# Peripherals.net
KiCad netlist of a schematic drawn in Altium Designer
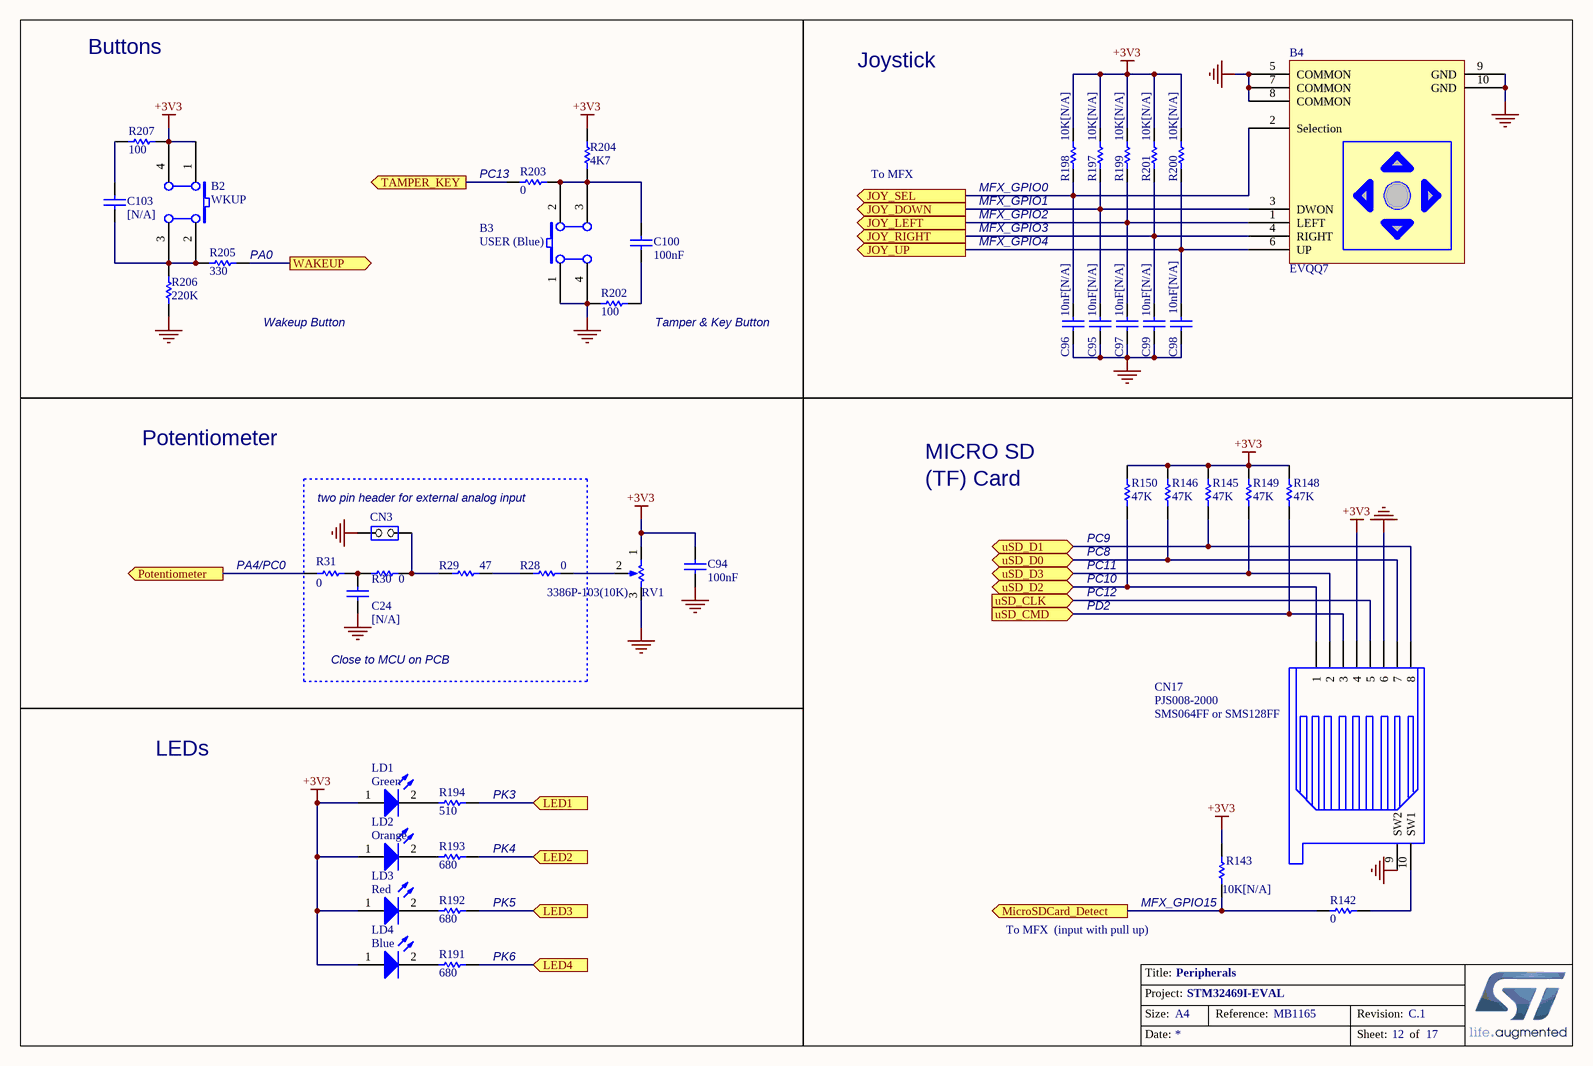
[diagram p0: Peripherals.SchDoc]

(export (version "E")
  (design (tool "Eeschema 10.0.6"))
  (components
    (comp (ref "B2")
      (value "WKUP")
      (footprint "PB10")
      (description "SE PUSHBUTTON")
      (libsource (lib "Documents") (part "SW PUSHBUTTON"))
    )
    (comp (ref "B3")
      (value "USER (Blue)")
      (footprint "PB10")
      (description "SE PUSHBUTTON")
      (libsource (lib "Documents") (part "SW PUSHBUTTON"))
    )
    (comp (ref "B4") (value "EVQQ7") (footprint "SW-JOY") (libsource (lib "mb1045") (part "EVQQ7")))
    (comp (ref "C24")
      (value "[N/A]")
      (footprint "0603C")
      (description "Capacitor")
      (fields (field (name "PUBLISHER") "Altium Limited"))
      (libsource (lib "Miscellaneous Devices") (part "cap"))
    )
    (comp (ref "C94")
      (value "100nF")
      (footprint "0603C")
      (description "Capacitor")
      (fields (field (name "PUBLISHER") "Altium Limited"))
      (libsource (lib "Miscellaneous Devices") (part "CAP"))
    )
    (comp (ref "C95")
      (value "10nF[N/A]")
      (footprint "0603C")
      (description "Capacitor")
      (fields (field (name "PUBLISHER") "Altium Limited"))
      (libsource (lib "Miscellaneous Devices") (part "CAP"))
    )
    (comp (ref "C96")
      (value "10nF[N/A]")
      (footprint "0603C")
      (description "Capacitor")
      (fields (field (name "PUBLISHER") "Altium Limited"))
      (libsource (lib "Miscellaneous Devices") (part "CAP"))
    )
    (comp (ref "C97")
      (value "10nF[N/A]")
      (footprint "0603C")
      (description "Capacitor")
      (fields (field (name "PUBLISHER") "Altium Limited"))
      (libsource (lib "Miscellaneous Devices") (part "CAP"))
    )
    (comp (ref "C98")
      (value "10nF[N/A]")
      (footprint "0603C")
      (description "Capacitor")
      (fields (field (name "PUBLISHER") "Altium Limited"))
      (libsource (lib "Miscellaneous Devices") (part "CAP"))
    )
    (comp (ref "C99")
      (value "10nF[N/A]")
      (footprint "0603C")
      (description "Capacitor")
      (fields (field (name "PUBLISHER") "Altium Limited"))
      (libsource (lib "Miscellaneous Devices") (part "CAP"))
    )
    (comp (ref "C100")
      (value "100nF")
      (footprint "0603C")
      (description "Capacitor")
      (fields (field (name "PUBLISHER") "Altium Limited"))
      (libsource (lib "Miscellaneous Devices") (part "CAP"))
    )
    (comp (ref "C103")
      (value "[N/A]")
      (footprint "0603C")
      (description "Capacitor")
      (fields (field (name "PUBLISHER") "Altium Limited"))
      (libsource (lib "Miscellaneous Devices") (part "CAP"))
    )
    (comp (ref "CN3") (value "~") (footprint "SIP2") (libsource (lib "*") (part "JP2")))
    (comp (ref "CN17")
      (value "PJS008-2000")
      (footprint "MSD_PJS008_")
      (libsource (lib "MB525") (part "SMS016AFA5E"))
    )
    (comp (ref "LD1")
      (value "Green")
      (footprint "0603D")
      (description "Typical RED, GREEN, YELLOW, AMBER GaAs LED")
      (fields (field (name "PUBLISHER") "Altium Limited"))
      (libsource (lib "Miscellaneous Devices") (part "LED2"))
    )
    (comp (ref "LD2")
      (value "Orange")
      (footprint "0603D")
      (description "Typical RED, GREEN, YELLOW, AMBER GaAs LED")
      (fields (field (name "PUBLISHER") "Altium Limited"))
      (libsource (lib "Miscellaneous Devices") (part "LED2"))
    )
    (comp (ref "LD3")
      (value "Red")
      (footprint "0603D")
      (description "Typical RED, GREEN, YELLOW, AMBER GaAs LED")
      (fields (field (name "PUBLISHER") "Altium Limited"))
      (libsource (lib "Miscellaneous Devices") (part "LED2"))
    )
    (comp (ref "LD4")
      (value "Blue")
      (footprint "0603D")
      (description "Typical RED, GREEN, YELLOW, AMBER GaAs LED")
      (fields (field (name "PUBLISHER") "Altium Limited"))
      (libsource (lib "Miscellaneous Devices") (part "LED2"))
    )
    (comp (ref "R28")
      (value "0")
      (footprint "0603R")
      (description "Resistor")
      (fields (field (name "PUBLISHER") "Altium Limited"))
      (libsource (lib "Miscellaneous Devices") (part "Res1"))
    )
    (comp (ref "R29")
      (value "47")
      (footprint "0603R")
      (description "Resistor")
      (fields (field (name "PUBLISHER") "Altium Limited"))
      (libsource (lib "Miscellaneous Devices") (part "Res1"))
    )
    (comp (ref "R30")
      (value "0")
      (footprint "0603R")
      (description "Resistor")
      (fields (field (name "PUBLISHER") "Altium Limited"))
      (libsource (lib "Miscellaneous Devices") (part "Res1"))
    )
    (comp (ref "R31")
      (value "0")
      (footprint "0603R")
      (description "Resistor")
      (fields (field (name "PUBLISHER") "Altium Limited"))
      (libsource (lib "Miscellaneous Devices") (part "Res1"))
    )
    (comp (ref "R142")
      (value "0")
      (footprint "0603R")
      (description "Resistor")
      (fields (field (name "PUBLISHER") "Altium Limited"))
      (libsource (lib "Miscellaneous Devices") (part "Res1"))
    )
    (comp (ref "R143")
      (value "10K[N/A]")
      (footprint "0603R")
      (description "Resistor")
      (fields (field (name "PUBLISHER") "Altium Limited"))
      (libsource (lib "Miscellaneous Devices") (part "Res1"))
    )
    (comp (ref "R145")
      (value "47K")
      (footprint "0603R")
      (description "Resistor")
      (fields (field (name "PUBLISHER") "Altium Limited"))
      (libsource (lib "Miscellaneous Devices") (part "res1"))
    )
    (comp (ref "R146")
      (value "47K")
      (footprint "0603R")
      (description "Resistor")
      (fields (field (name "PUBLISHER") "Altium Limited"))
      (libsource (lib "Miscellaneous Devices") (part "res1"))
    )
    (comp (ref "R148")
      (value "47K")
      (footprint "0603R")
      (description "Resistor")
      (fields (field (name "PUBLISHER") "Altium Limited"))
      (libsource (lib "Miscellaneous Devices") (part "res1"))
    )
    (comp (ref "R149")
      (value "47K")
      (footprint "0603R")
      (description "Resistor")
      (fields (field (name "PUBLISHER") "Altium Limited"))
      (libsource (lib "Miscellaneous Devices") (part "res1"))
    )
    (comp (ref "R150")
      (value "47K")
      (footprint "0603R")
      (description "Resistor")
      (fields (field (name "PUBLISHER") "Altium Limited"))
      (libsource (lib "Miscellaneous Devices") (part "res1"))
    )
    (comp (ref "R191")
      (value "680")
      (footprint "0603R")
      (description "Resistor")
      (fields (field (name "PUBLISHER") "Altium Limited"))
      (libsource (lib "Miscellaneous Devices") (part "Res1"))
    )
    (comp (ref "R192")
      (value "680")
      (footprint "0603R")
      (description "Resistor")
      (fields (field (name "PUBLISHER") "Altium Limited"))
      (libsource (lib "Miscellaneous Devices") (part "Res1"))
    )
    (comp (ref "R193")
      (value "680")
      (footprint "0603R")
      (description "Resistor")
      (fields (field (name "PUBLISHER") "Altium Limited"))
      (libsource (lib "Miscellaneous Devices") (part "Res1"))
    )
    (comp (ref "R194")
      (value "510")
      (footprint "0603R")
      (description "Resistor")
      (fields (field (name "PUBLISHER") "Altium Limited"))
      (libsource (lib "Miscellaneous Devices") (part "Res1"))
    )
    (comp (ref "R197")
      (value "10K[N/A]")
      (footprint "0603R")
      (description "Resistor")
      (fields (field (name "PUBLISHER") "Altium Limited"))
      (libsource (lib "Miscellaneous Devices") (part "res1"))
    )
    (comp (ref "R198")
      (value "10K[N/A]")
      (footprint "0603R")
      (description "Resistor")
      (fields (field (name "PUBLISHER") "Altium Limited"))
      (libsource (lib "Miscellaneous Devices") (part "res1"))
    )
    (comp (ref "R199")
      (value "10K[N/A]")
      (footprint "0603R")
      (description "Resistor")
      (fields (field (name "PUBLISHER") "Altium Limited"))
      (libsource (lib "Miscellaneous Devices") (part "res1"))
    )
    (comp (ref "R200")
      (value "10K[N/A]")
      (footprint "0603R")
      (description "Resistor")
      (fields (field (name "PUBLISHER") "Altium Limited"))
      (libsource (lib "Miscellaneous Devices") (part "res1"))
    )
    (comp (ref "R201")
      (value "10K[N/A]")
      (footprint "0603R")
      (description "Resistor")
      (fields (field (name "PUBLISHER") "Altium Limited"))
      (libsource (lib "Miscellaneous Devices") (part "res1"))
    )
    (comp (ref "R202")
      (value "100")
      (footprint "0603R")
      (description "Resistor")
      (fields (field (name "PUBLISHER") "Altium Limited"))
      (libsource (lib "Miscellaneous Devices") (part "Res1"))
    )
    (comp (ref "R203")
      (value "0")
      (footprint "0603R")
      (description "Resistor")
      (fields (field (name "PUBLISHER") "Altium Limited"))
      (libsource (lib "Miscellaneous Devices") (part "Res1"))
    )
    (comp (ref "R204")
      (value "4K7")
      (footprint "0603R")
      (description "Resistor")
      (fields (field (name "PUBLISHER") "Altium Limited"))
      (libsource (lib "Miscellaneous Devices") (part "res1"))
    )
    (comp (ref "R205")
      (value "330")
      (footprint "0603R")
      (description "Resistor")
      (fields (field (name "PUBLISHER") "Altium Limited"))
      (libsource (lib "Miscellaneous Devices") (part "Res1"))
    )
    (comp (ref "R206")
      (value "220K")
      (footprint "0603R")
      (description "Resistor")
      (fields (field (name "PUBLISHER") "Altium Limited"))
      (libsource (lib "Miscellaneous Devices") (part "res1"))
    )
    (comp (ref "R207")
      (value "100")
      (footprint "0603R")
      (description "Resistor")
      (fields (field (name "PUBLISHER") "Altium Limited"))
      (libsource (lib "Miscellaneous Devices") (part "Res1"))
    )
    (comp (ref "RV1")
      (value "3386P-103(10K)")
      (footprint "3386P")
      (libsource (lib "STR910_SCHLIB") (part "RV"))
    )
  )
  (nets
    (net (code "1") (name "+3V3") (class "Default")
      (node (ref "B2") (pin "1") (pinfunction "A0_1") (pintype "passive"))
      (node (ref "B2") (pin "4") (pinfunction "A1_4") (pintype "passive"))
      (node (ref "C94") (pin "1") (pinfunction "1_1") (pintype "passive"))
      (node (ref "CN17") (pin "4") (pinfunction "4_4") (pintype "passive"))
      (node (ref "LD1") (pin "1") (pinfunction "A_1") (pintype "passive"))
      (node (ref "LD2") (pin "1") (pinfunction "A_1") (pintype "passive"))
      (node (ref "LD3") (pin "1") (pinfunction "A_1") (pintype "passive"))
      (node (ref "LD4") (pin "1") (pinfunction "A_1") (pintype "passive"))
      (node (ref "R143") (pin "2") (pinfunction "2_2") (pintype "passive"))
      (node (ref "R145") (pin "1") (pinfunction "1_1") (pintype "passive"))
      (node (ref "R146") (pin "1") (pinfunction "1_1") (pintype "passive"))
      (node (ref "R148") (pin "1") (pinfunction "1_1") (pintype "passive"))
      (node (ref "R149") (pin "1") (pinfunction "1_1") (pintype "passive"))
      (node (ref "R150") (pin "1") (pinfunction "1_1") (pintype "passive"))
      (node (ref "R197") (pin "1") (pinfunction "1_1") (pintype "passive"))
      (node (ref "R198") (pin "1") (pinfunction "1_1") (pintype "passive"))
      (node (ref "R199") (pin "1") (pinfunction "1_1") (pintype "passive"))
      (node (ref "R200") (pin "1") (pinfunction "1_1") (pintype "passive"))
      (node (ref "R201") (pin "1") (pinfunction "1_1") (pintype "passive"))
      (node (ref "R204") (pin "2") (pinfunction "2_2") (pintype "passive"))
      (node (ref "R207") (pin "1") (pinfunction "1_1") (pintype "passive"))
      (node (ref "RV1") (pin "1") (pinfunction "BOT_1") (pintype "passive"))
    )
    (net (code "2") (name "/JOY_DOWN") (class "Default")
      (node (ref "B4") (pin "3") (pinfunction "DWON_3") (pintype "passive"))
      (node (ref "C95") (pin "2") (pinfunction "2_2") (pintype "passive"))
      (node (ref "R197") (pin "2") (pinfunction "2_2") (pintype "passive"))
    )
    (net (code "3") (name "/JOY_LEFT") (class "Default")
      (node (ref "B4") (pin "1") (pinfunction "LEFT_1") (pintype "passive"))
      (node (ref "C97") (pin "2") (pinfunction "2_2") (pintype "passive"))
      (node (ref "R199") (pin "2") (pinfunction "2_2") (pintype "passive"))
    )
    (net (code "4") (name "/JOY_RIGHT") (class "Default")
      (node (ref "B4") (pin "4") (pinfunction "RIGHT_4") (pintype "passive"))
      (node (ref "C99") (pin "2") (pinfunction "2_2") (pintype "passive"))
      (node (ref "R201") (pin "2") (pinfunction "2_2") (pintype "passive"))
    )
    (net (code "5") (name "/JOY_SEL") (class "Default")
      (node (ref "B4") (pin "2") (pinfunction "Selection_2") (pintype "passive"))
      (node (ref "C96") (pin "2") (pinfunction "2_2") (pintype "passive"))
      (node (ref "R198") (pin "2") (pinfunction "2_2") (pintype "passive"))
    )
    (net (code "6") (name "/JOY_UP") (class "Default")
      (node (ref "B4") (pin "6") (pinfunction "UP_6") (pintype "passive"))
      (node (ref "C98") (pin "2") (pinfunction "2_2") (pintype "passive"))
      (node (ref "R200") (pin "2") (pinfunction "2_2") (pintype "passive"))
    )
    (net (code "7") (name "/LED1") (class "Default")
      (node (ref "R194") (pin "1") (pinfunction "1_1") (pintype "passive"))
    )
    (net (code "8") (name "/LED2") (class "Default")
      (node (ref "R193") (pin "1") (pinfunction "1_1") (pintype "passive"))
    )
    (net (code "9") (name "/LED3") (class "Default")
      (node (ref "R192") (pin "1") (pinfunction "1_1") (pintype "passive"))
    )
    (net (code "10") (name "/LED4") (class "Default")
      (node (ref "R191") (pin "1") (pinfunction "1_1") (pintype "passive"))
    )
    (net (code "11") (name "/MicroSDCard_Detect") (class "Default")
      (node (ref "R142") (pin "1") (pinfunction "1_1") (pintype "passive"))
      (node (ref "R143") (pin "1") (pinfunction "1_1") (pintype "passive"))
    )
    (net (code "12") (name "/Potentiometer") (class "Default")
      (node (ref "R31") (pin "2") (pinfunction "2_2") (pintype "passive"))
    )
    (net (code "13") (name "/TAMPER_KEY") (class "Default")
      (node (ref "R203") (pin "2") (pinfunction "2_2") (pintype "passive"))
    )
    (net (code "14") (name "/WAKEUP") (class "Default")
      (node (ref "R205") (pin "2") (pinfunction "2_2") (pintype "passive"))
    )
    (net (code "15") (name "/uSD_CLK") (class "Default")
      (node (ref "CN17") (pin "5") (pinfunction "5_5") (pintype "passive"))
    )
    (net (code "16") (name "/uSD_CMD") (class "Default")
      (node (ref "CN17") (pin "3") (pinfunction "3_3") (pintype "passive"))
      (node (ref "R148") (pin "2") (pinfunction "2_2") (pintype "passive"))
    )
    (net (code "17") (name "/uSD_D0") (class "Default")
      (node (ref "CN17") (pin "7") (pinfunction "7_7") (pintype "passive"))
      (node (ref "R146") (pin "2") (pinfunction "2_2") (pintype "passive"))
    )
    (net (code "18") (name "/uSD_D1") (class "Default")
      (node (ref "CN17") (pin "8") (pinfunction "8_8") (pintype "passive"))
      (node (ref "R145") (pin "2") (pinfunction "2_2") (pintype "passive"))
    )
    (net (code "19") (name "/uSD_D2") (class "Default")
      (node (ref "CN17") (pin "1") (pinfunction "1_1") (pintype "passive"))
      (node (ref "R150") (pin "2") (pinfunction "2_2") (pintype "passive"))
    )
    (net (code "20") (name "/uSD_D3") (class "Default")
      (node (ref "CN17") (pin "2") (pinfunction "2_2") (pintype "passive"))
      (node (ref "R149") (pin "2") (pinfunction "2_2") (pintype "passive"))
    )
    (net (code "21") (name "GND") (class "Default")
      (node (ref "B3") (pin "1") (pinfunction "A0_1") (pintype "passive"))
      (node (ref "B3") (pin "4") (pinfunction "A1_4") (pintype "passive"))
      (node (ref "B4") (pin "10") (pinfunction "GND_10") (pintype "passive"))
      (node (ref "B4") (pin "5") (pinfunction "COMMON_5") (pintype "passive"))
      (node (ref "B4") (pin "7") (pinfunction "COMMON_7") (pintype "passive"))
      (node (ref "B4") (pin "8") (pinfunction "COMMON_8") (pintype "passive"))
      (node (ref "B4") (pin "9") (pinfunction "GND_9") (pintype "passive"))
      (node (ref "C24") (pin "1") (pinfunction "1_1") (pintype "passive"))
      (node (ref "C94") (pin "2") (pinfunction "2_2") (pintype "passive"))
      (node (ref "C95") (pin "1") (pinfunction "1_1") (pintype "passive"))
      (node (ref "C96") (pin "1") (pinfunction "1_1") (pintype "passive"))
      (node (ref "C97") (pin "1") (pinfunction "1_1") (pintype "passive"))
      (node (ref "C98") (pin "1") (pinfunction "1_1") (pintype "passive"))
      (node (ref "C99") (pin "1") (pinfunction "1_1") (pintype "passive"))
      (node (ref "CN17") (pin "6") (pinfunction "6_6") (pintype "passive"))
      (node (ref "CN17") (pin "9") (pinfunction "SW2_9") (pintype "passive"))
      (node (ref "CN3") (pin "2") (pinfunction "NO_2") (pintype "passive"))
      (node (ref "R202") (pin "1") (pinfunction "1_1") (pintype "passive"))
      (node (ref "R206") (pin "2") (pinfunction "2_2") (pintype "passive"))
      (node (ref "RV1") (pin "3") (pinfunction "TOP_3") (pintype "passive"))
    )
    (net (code "22") (name "Net-(B2-B0)") (class "Default")
      (node (ref "B2") (pin "2") (pinfunction "B0_2") (pintype "passive"))
      (node (ref "B2") (pin "3") (pinfunction "B1_3") (pintype "passive"))
      (node (ref "C103") (pin "2") (pinfunction "2_2") (pintype "passive"))
      (node (ref "R205") (pin "1") (pinfunction "1_1") (pintype "passive"))
      (node (ref "R206") (pin "1") (pinfunction "1_1") (pintype "passive"))
    )
    (net (code "23") (name "Net-(B3-B0)") (class "Default")
      (node (ref "B3") (pin "2") (pinfunction "B0_2") (pintype "passive"))
      (node (ref "B3") (pin "3") (pinfunction "B1_3") (pintype "passive"))
      (node (ref "C100") (pin "2") (pinfunction "2_2") (pintype "passive"))
      (node (ref "R203") (pin "1") (pinfunction "1_1") (pintype "passive"))
      (node (ref "R204") (pin "1") (pinfunction "1_1") (pintype "passive"))
    )
    (net (code "24") (name "Net-(C24-Pad2)") (class "Default")
      (node (ref "C24") (pin "2") (pinfunction "2_2") (pintype "passive"))
      (node (ref "R30") (pin "1") (pinfunction "1_1") (pintype "passive"))
      (node (ref "R31") (pin "1") (pinfunction "1_1") (pintype "passive"))
    )
    (net (code "25") (name "Net-(C100-Pad1)") (class "Default")
      (node (ref "C100") (pin "1") (pinfunction "1_1") (pintype "passive"))
      (node (ref "R202") (pin "2") (pinfunction "2_2") (pintype "passive"))
    )
    (net (code "26") (name "Net-(C103-Pad1)") (class "Default")
      (node (ref "C103") (pin "1") (pinfunction "1_1") (pintype "passive"))
      (node (ref "R207") (pin "2") (pinfunction "2_2") (pintype "passive"))
    )
    (net (code "27") (name "Net-(CN3-COMMON)") (class "Default")
      (node (ref "CN3") (pin "1") (pinfunction "COMMON_1") (pintype "passive"))
      (node (ref "R29") (pin "1") (pinfunction "1_1") (pintype "passive"))
      (node (ref "R30") (pin "2") (pinfunction "2_2") (pintype "passive"))
    )
    (net (code "28") (name "Net-(CN17-SW1)") (class "Default")
      (node (ref "CN17") (pin "10") (pinfunction "SW1_10") (pintype "passive"))
      (node (ref "R142") (pin "2") (pinfunction "2_2") (pintype "passive"))
    )
    (net (code "29") (name "Net-(LD1-K)") (class "Default")
      (node (ref "LD1") (pin "2") (pinfunction "K_2") (pintype "passive"))
      (node (ref "R194") (pin "2") (pinfunction "2_2") (pintype "passive"))
    )
    (net (code "30") (name "Net-(LD2-K)") (class "Default")
      (node (ref "LD2") (pin "2") (pinfunction "K_2") (pintype "passive"))
      (node (ref "R193") (pin "2") (pinfunction "2_2") (pintype "passive"))
    )
    (net (code "31") (name "Net-(LD3-K)") (class "Default")
      (node (ref "LD3") (pin "2") (pinfunction "K_2") (pintype "passive"))
      (node (ref "R192") (pin "2") (pinfunction "2_2") (pintype "passive"))
    )
    (net (code "32") (name "Net-(LD4-K)") (class "Default")
      (node (ref "LD4") (pin "2") (pinfunction "K_2") (pintype "passive"))
      (node (ref "R191") (pin "2") (pinfunction "2_2") (pintype "passive"))
    )
    (net (code "33") (name "Net-(R28-Pad1)") (class "Default")
      (node (ref "R28") (pin "1") (pinfunction "1_1") (pintype "passive"))
      (node (ref "R29") (pin "2") (pinfunction "2_2") (pintype "passive"))
    )
    (net (code "34") (name "Net-(RV1-TAP)") (class "Default")
      (node (ref "R28") (pin "2") (pinfunction "2_2") (pintype "passive"))
      (node (ref "RV1") (pin "2") (pinfunction "TAP_2") (pintype "passive"))
    )
  )
)
